# SDRAM.net
KiCad netlist of a schematic drawn in Altium Designer
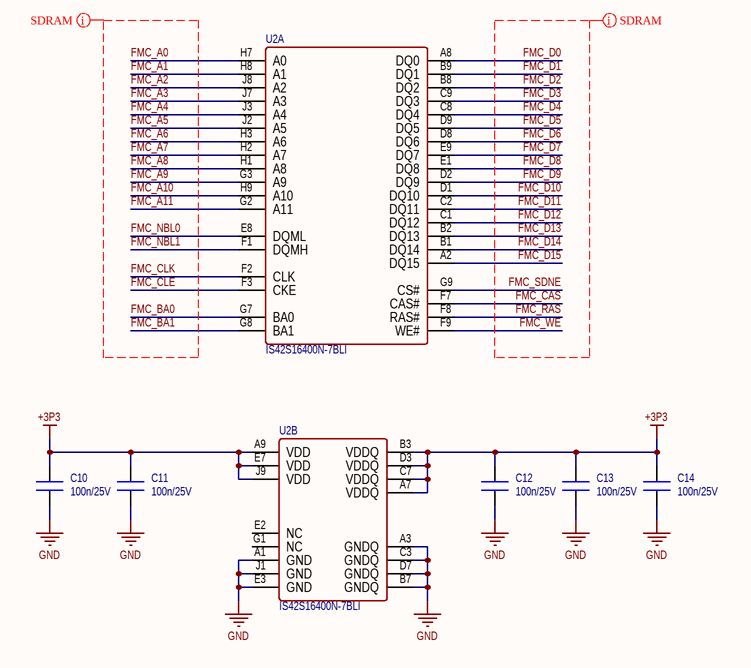
[diagram p0: SDRAM.SchDoc]

(export (version "E")
  (design (tool "Eeschema 10.0.6"))
  (components
    (comp (ref "C10")
      (value "100n/25V")
      (footprint "CN-SMD-0603")
      (description "CL10B104KA8NNNC")
      (libsource (lib "Library") (part "CN"))
    )
    (comp (ref "C11")
      (value "100n/25V")
      (footprint "CN-SMD-0603")
      (description "CL10B104KA8NNNC")
      (libsource (lib "Library") (part "CN"))
    )
    (comp (ref "C12")
      (value "100n/25V")
      (footprint "CN-SMD-0603")
      (description "CL10B104KA8NNNC")
      (libsource (lib "Library") (part "CN"))
    )
    (comp (ref "C13")
      (value "100n/25V")
      (footprint "CN-SMD-0603")
      (description "CL10B104KA8NNNC")
      (libsource (lib "Library") (part "CN"))
    )
    (comp (ref "C14")
      (value "100n/25V")
      (footprint "CN-SMD-0603")
      (description "CL10B104KA8NNNC")
      (libsource (lib "Library") (part "CN"))
    )
    (comp (ref "U2")
      (value "IS42S16400N-7BLI")
      (footprint "BGA54C80P9X6_800X800X120")
      (description "1 Meg Bits x 16 Bits x 4 Banks (64-MBIT) SYNCHRONOUS DYNAMIC RAM")
      (libsource (lib "Library") (part "IS42S16400N-7BLI"))
    )
  )
  (nets
    (net (code "1") (name "+3P3") (class "Default")
      (node (ref "C10") (pin "2") (pinfunction "2_2") (pintype "passive"))
      (node (ref "C11") (pin "2") (pinfunction "2_2") (pintype "passive"))
      (node (ref "C12") (pin "2") (pinfunction "2_2") (pintype "passive"))
      (node (ref "C13") (pin "2") (pinfunction "2_2") (pintype "passive"))
      (node (ref "C14") (pin "2") (pinfunction "2_2") (pintype "passive"))
      (node (ref "U2") (pin "A7") (pinfunction "VDDQ_A7") (pintype "passive"))
      (node (ref "U2") (pin "A9") (pinfunction "VDD_A9") (pintype "passive"))
      (node (ref "U2") (pin "B3") (pinfunction "VDDQ_B3") (pintype "passive"))
      (node (ref "U2") (pin "C7") (pinfunction "VDDQ_C7") (pintype "passive"))
      (node (ref "U2") (pin "D3") (pinfunction "VDDQ_D3") (pintype "passive"))
      (node (ref "U2") (pin "E7") (pinfunction "VDD_E7") (pintype "passive"))
      (node (ref "U2") (pin "J9") (pinfunction "VDD_J9") (pintype "passive"))
    )
    (net (code "2") (name "/FMC_A0") (class "Default")
      (node (ref "U2") (pin "H7") (pinfunction "A0_H7") (pintype "passive"))
    )
    (net (code "3") (name "/FMC_A1") (class "Default")
      (node (ref "U2") (pin "H8") (pinfunction "A1_H8") (pintype "passive"))
    )
    (net (code "4") (name "/FMC_A2") (class "Default")
      (node (ref "U2") (pin "J8") (pinfunction "A2_J8") (pintype "passive"))
    )
    (net (code "5") (name "/FMC_A3") (class "Default")
      (node (ref "U2") (pin "J7") (pinfunction "A3_J7") (pintype "passive"))
    )
    (net (code "6") (name "/FMC_A4") (class "Default")
      (node (ref "U2") (pin "J3") (pinfunction "A4_J3") (pintype "passive"))
    )
    (net (code "7") (name "/FMC_A5") (class "Default")
      (node (ref "U2") (pin "J2") (pinfunction "A5_J2") (pintype "passive"))
    )
    (net (code "8") (name "/FMC_A6") (class "Default")
      (node (ref "U2") (pin "H3") (pinfunction "A6_H3") (pintype "passive"))
    )
    (net (code "9") (name "/FMC_A7") (class "Default")
      (node (ref "U2") (pin "H2") (pinfunction "A7_H2") (pintype "passive"))
    )
    (net (code "10") (name "/FMC_A8") (class "Default")
      (node (ref "U2") (pin "H1") (pinfunction "A8_H1") (pintype "passive"))
    )
    (net (code "11") (name "/FMC_A9") (class "Default")
      (node (ref "U2") (pin "G3") (pinfunction "A9_G3") (pintype "passive"))
    )
    (net (code "12") (name "/FMC_A10") (class "Default")
      (node (ref "U2") (pin "H9") (pinfunction "A10_H9") (pintype "passive"))
    )
    (net (code "13") (name "/FMC_A11") (class "Default")
      (node (ref "U2") (pin "G2") (pinfunction "A11_G2") (pintype "passive"))
    )
    (net (code "14") (name "/FMC_BA0") (class "Default")
      (node (ref "U2") (pin "G7") (pinfunction "BA0_G7") (pintype "passive"))
    )
    (net (code "15") (name "/FMC_BA1") (class "Default")
      (node (ref "U2") (pin "G8") (pinfunction "BA1_G8") (pintype "passive"))
    )
    (net (code "16") (name "/FMC_CAS") (class "Default")
      (node (ref "U2") (pin "F7") (pinfunction "CAS#_F7") (pintype "passive"))
    )
    (net (code "17") (name "/FMC_CLE") (class "Default")
      (node (ref "U2") (pin "F3") (pinfunction "CKE_F3") (pintype "passive"))
    )
    (net (code "18") (name "/FMC_CLK") (class "Default")
      (node (ref "U2") (pin "F2") (pinfunction "CLK_F2") (pintype "passive"))
    )
    (net (code "19") (name "/FMC_D0") (class "Default")
      (node (ref "U2") (pin "A8") (pinfunction "DQ0_A8") (pintype "passive"))
    )
    (net (code "20") (name "/FMC_D1") (class "Default")
      (node (ref "U2") (pin "B9") (pinfunction "DQ1_B9") (pintype "passive"))
    )
    (net (code "21") (name "/FMC_D2") (class "Default")
      (node (ref "U2") (pin "B8") (pinfunction "DQ2_B8") (pintype "passive"))
    )
    (net (code "22") (name "/FMC_D3") (class "Default")
      (node (ref "U2") (pin "C9") (pinfunction "DQ3_C9") (pintype "passive"))
    )
    (net (code "23") (name "/FMC_D4") (class "Default")
      (node (ref "U2") (pin "C8") (pinfunction "DQ4_C8") (pintype "passive"))
    )
    (net (code "24") (name "/FMC_D5") (class "Default")
      (node (ref "U2") (pin "D9") (pinfunction "DQ5_D9") (pintype "passive"))
    )
    (net (code "25") (name "/FMC_D6") (class "Default")
      (node (ref "U2") (pin "D8") (pinfunction "DQ6_D8") (pintype "passive"))
    )
    (net (code "26") (name "/FMC_D7") (class "Default")
      (node (ref "U2") (pin "E9") (pinfunction "DQ7_E9") (pintype "passive"))
    )
    (net (code "27") (name "/FMC_D8") (class "Default")
      (node (ref "U2") (pin "E1") (pinfunction "DQ8_E1") (pintype "passive"))
    )
    (net (code "28") (name "/FMC_D9") (class "Default")
      (node (ref "U2") (pin "D2") (pinfunction "DQ9_D2") (pintype "passive"))
    )
    (net (code "29") (name "/FMC_D10") (class "Default")
      (node (ref "U2") (pin "D1") (pinfunction "DQ10_D1") (pintype "passive"))
    )
    (net (code "30") (name "/FMC_D11") (class "Default")
      (node (ref "U2") (pin "C2") (pinfunction "DQ11_C2") (pintype "passive"))
    )
    (net (code "31") (name "/FMC_D12") (class "Default")
      (node (ref "U2") (pin "C1") (pinfunction "DQ12_C1") (pintype "passive"))
    )
    (net (code "32") (name "/FMC_D13") (class "Default")
      (node (ref "U2") (pin "B2") (pinfunction "DQ13_B2") (pintype "passive"))
    )
    (net (code "33") (name "/FMC_D14") (class "Default")
      (node (ref "U2") (pin "B1") (pinfunction "DQ14_B1") (pintype "passive"))
    )
    (net (code "34") (name "/FMC_D15") (class "Default")
      (node (ref "U2") (pin "A2") (pinfunction "DQ15_A2") (pintype "passive"))
    )
    (net (code "35") (name "/FMC_NBL0") (class "Default")
      (node (ref "U2") (pin "E8") (pinfunction "DQML_E8") (pintype "passive"))
    )
    (net (code "36") (name "/FMC_NBL1") (class "Default")
      (node (ref "U2") (pin "F1") (pinfunction "DQMH_F1") (pintype "passive"))
    )
    (net (code "37") (name "/FMC_RAS") (class "Default")
      (node (ref "U2") (pin "F8") (pinfunction "RAS#_F8") (pintype "passive"))
    )
    (net (code "38") (name "/FMC_SDNE") (class "Default")
      (node (ref "U2") (pin "G9") (pinfunction "CS#_G9") (pintype "passive"))
    )
    (net (code "39") (name "/FMC_WE") (class "Default")
      (node (ref "U2") (pin "F9") (pinfunction "WE#_F9") (pintype "passive"))
    )
    (net (code "40") (name "GND") (class "Default")
      (node (ref "C10") (pin "1") (pinfunction "1_1") (pintype "passive"))
      (node (ref "C11") (pin "1") (pinfunction "1_1") (pintype "passive"))
      (node (ref "C12") (pin "1") (pinfunction "1_1") (pintype "passive"))
      (node (ref "C13") (pin "1") (pinfunction "1_1") (pintype "passive"))
      (node (ref "C14") (pin "1") (pinfunction "1_1") (pintype "passive"))
      (node (ref "U2") (pin "A1") (pinfunction "GND_A1") (pintype "passive"))
      (node (ref "U2") (pin "A3") (pinfunction "GNDQ_A3") (pintype "passive"))
      (node (ref "U2") (pin "B7") (pinfunction "GNDQ_B7") (pintype "passive"))
      (node (ref "U2") (pin "C3") (pinfunction "GNDQ_C3") (pintype "passive"))
      (node (ref "U2") (pin "D7") (pinfunction "GNDQ_D7") (pintype "passive"))
      (node (ref "U2") (pin "E3") (pinfunction "GND_E3") (pintype "passive"))
      (node (ref "U2") (pin "J1") (pinfunction "GND_J1") (pintype "passive"))
    )
    (net (code "41") (name "unconnected-(U2B-NC-PadE2)") (class "Default")
      (node (ref "U2") (pin "E2") (pinfunction "NC_E2") (pintype "passive"))
    )
    (net (code "42") (name "unconnected-(U2B-NC-PadG1)") (class "Default")
      (node (ref "U2") (pin "G1") (pinfunction "NC_G1") (pintype "passive"))
    )
  )
)
